# SCH_V2.net
KiCad netlist of a schematic drawn in Altium Designer
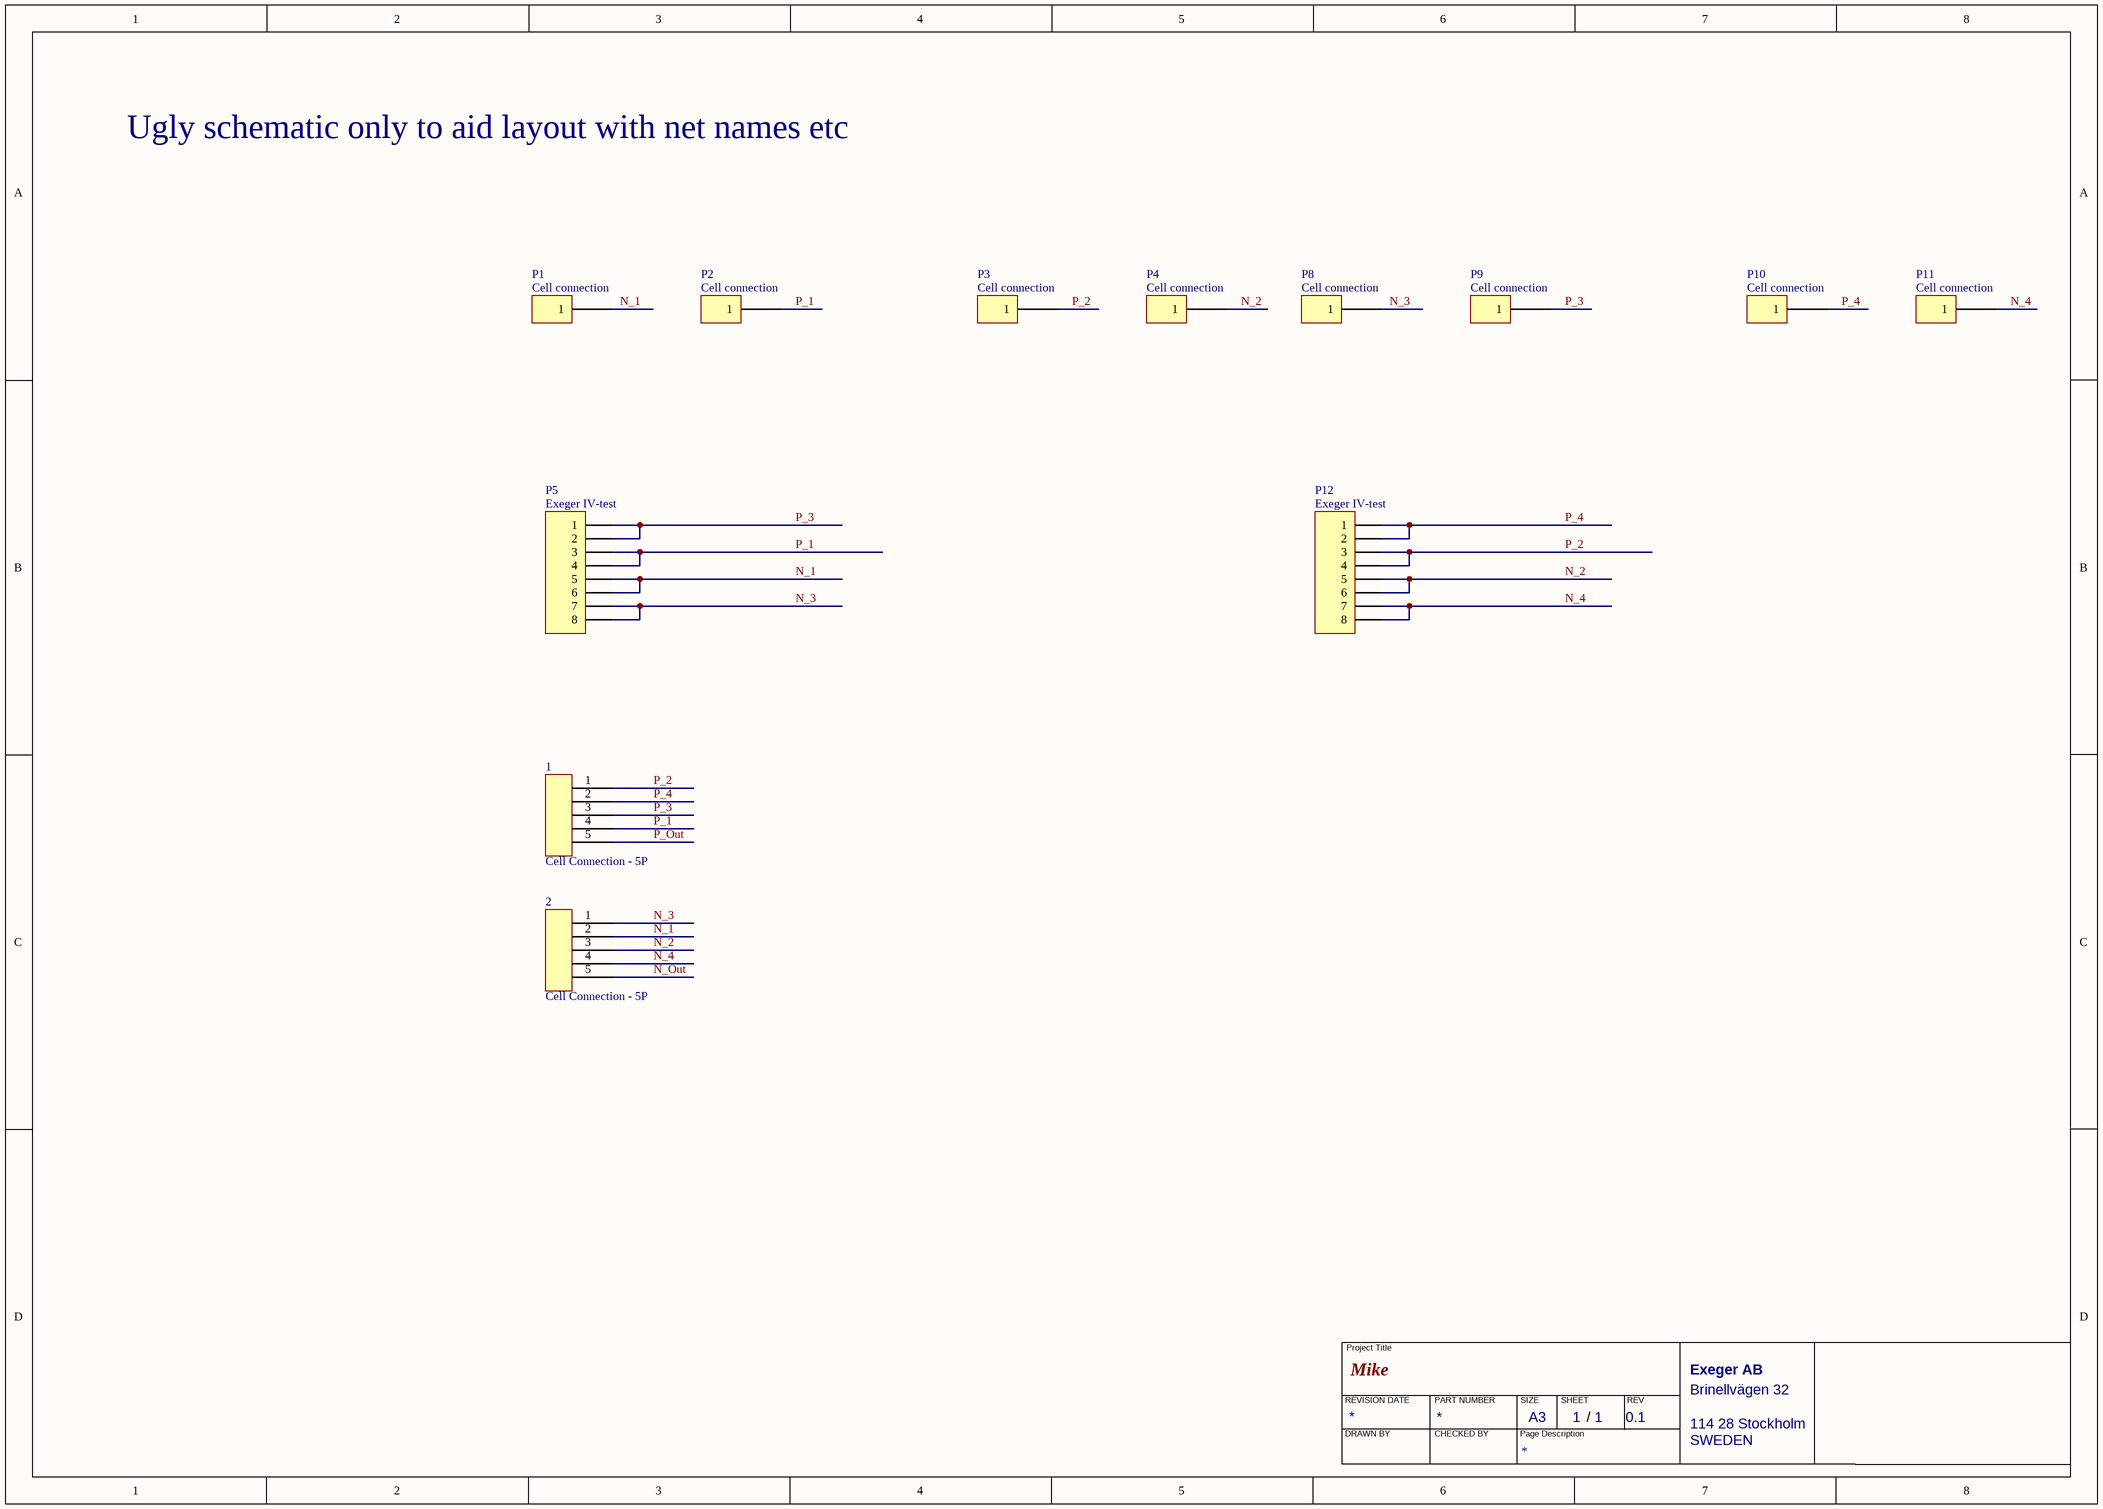
[diagram p0: SCH_V2.SchDoc]

(export (version "E")
  (design (tool "Eeschema 10.0.6"))
  (components
    (comp (ref "1")
      (value "Cell Connection - 5P")
      (footprint "4-To-1-Connector")
      (libsource (lib "Flex_SCH_symbols") (part "Cell Connection - 5P"))
    )
    (comp (ref "2")
      (value "Cell Connection - 5P")
      (footprint "4-To-1-Connector")
      (libsource (lib "Flex_SCH_symbols") (part "Cell Connection - 5P"))
    )
    (comp (ref "P1")
      (value "Cell connection")
      (footprint "Cell_pad_4mm_SM0.5mm")
      (libsource (lib "Flex_SCH_symbols") (part "Cell connection 1P"))
    )
    (comp (ref "P2")
      (value "Cell connection")
      (footprint "Cell_pad_4mm_SM0.5mm")
      (libsource (lib "Flex_SCH_symbols") (part "Cell connection 1P"))
    )
    (comp (ref "P3")
      (value "Cell connection")
      (footprint "Cell_pad_4mm_SM0.5mm")
      (libsource (lib "Flex_SCH_symbols") (part "Cell connection 1P"))
    )
    (comp (ref "P4")
      (value "Cell connection")
      (footprint "Cell_pad_4mm_SM0.5mm")
      (libsource (lib "Flex_SCH_symbols") (part "Cell connection 1P"))
    )
    (comp (ref "P5")
      (value "Exeger IV-test")
      (footprint "EXEGER_IV_8_PIN_NO_STIFF_ISOL_0.4")
      (description "Header, 8-Pin")
      (libsource (lib "Miscellaneous Connectors") (part "Header 8"))
    )
    (comp (ref "P8")
      (value "Cell connection")
      (footprint "Cell_pad_4mm_SM0.5mm")
      (libsource (lib "Flex_SCH_symbols") (part "Cell connection 1P"))
    )
    (comp (ref "P9")
      (value "Cell connection")
      (footprint "Cell_pad_4mm_SM0.5mm")
      (libsource (lib "Flex_SCH_symbols") (part "Cell connection 1P"))
    )
    (comp (ref "P10")
      (value "Cell connection")
      (footprint "Cell_pad_4mm_SM0.5mm")
      (libsource (lib "Flex_SCH_symbols") (part "Cell connection 1P"))
    )
    (comp (ref "P11")
      (value "Cell connection")
      (footprint "Cell_pad_4mm_SM0.5mm")
      (libsource (lib "Flex_SCH_symbols") (part "Cell connection 1P"))
    )
    (comp (ref "P12")
      (value "Exeger IV-test")
      (footprint "EXEGER_IV_8_PIN_NO_STIFF_ISOL_0.4")
      (description "Header, 8-Pin")
      (libsource (lib "Miscellaneous Connectors") (part "Header 8"))
    )
  )
  (nets
    (net (code "1") (name "/N_1") (class "Default")
      (node (ref "2") (pin "2") (pintype "passive"))
      (node (ref "P1") (pin "1") (pinfunction "1_1") (pintype "passive"))
      (node (ref "P5") (pin "5") (pinfunction "5_5") (pintype "passive"))
      (node (ref "P5") (pin "6") (pinfunction "6_6") (pintype "passive"))
    )
    (net (code "2") (name "/N_2") (class "Default")
      (node (ref "2") (pin "3") (pintype "passive"))
      (node (ref "P12") (pin "5") (pinfunction "5_5") (pintype "passive"))
      (node (ref "P12") (pin "6") (pinfunction "6_6") (pintype "passive"))
      (node (ref "P4") (pin "1") (pinfunction "1_1") (pintype "passive"))
    )
    (net (code "3") (name "/N_3") (class "Default")
      (node (ref "2") (pin "1") (pintype "passive"))
      (node (ref "P5") (pin "7") (pinfunction "7_7") (pintype "passive"))
      (node (ref "P5") (pin "8") (pinfunction "8_8") (pintype "passive"))
      (node (ref "P8") (pin "1") (pinfunction "1_1") (pintype "passive"))
    )
    (net (code "4") (name "/N_4") (class "Default")
      (node (ref "2") (pin "4") (pintype "passive"))
      (node (ref "P11") (pin "1") (pinfunction "1_1") (pintype "passive"))
      (node (ref "P12") (pin "7") (pinfunction "7_7") (pintype "passive"))
      (node (ref "P12") (pin "8") (pinfunction "8_8") (pintype "passive"))
    )
    (net (code "5") (name "/N_Out") (class "Default") (node (ref "2") (pin "5") (pintype "passive")))
    (net (code "6") (name "/P_1") (class "Default")
      (node (ref "1") (pin "4") (pintype "passive"))
      (node (ref "P2") (pin "1") (pinfunction "1_1") (pintype "passive"))
      (node (ref "P5") (pin "3") (pinfunction "3_3") (pintype "passive"))
      (node (ref "P5") (pin "4") (pinfunction "4_4") (pintype "passive"))
    )
    (net (code "7") (name "/P_2") (class "Default")
      (node (ref "1") (pin "1") (pintype "passive"))
      (node (ref "P12") (pin "3") (pinfunction "3_3") (pintype "passive"))
      (node (ref "P12") (pin "4") (pinfunction "4_4") (pintype "passive"))
      (node (ref "P3") (pin "1") (pinfunction "1_1") (pintype "passive"))
    )
    (net (code "8") (name "/P_3") (class "Default")
      (node (ref "1") (pin "3") (pintype "passive"))
      (node (ref "P5") (pin "1") (pinfunction "1_1") (pintype "passive"))
      (node (ref "P5") (pin "2") (pinfunction "2_2") (pintype "passive"))
      (node (ref "P9") (pin "1") (pinfunction "1_1") (pintype "passive"))
    )
    (net (code "9") (name "/P_4") (class "Default")
      (node (ref "1") (pin "2") (pintype "passive"))
      (node (ref "P10") (pin "1") (pinfunction "1_1") (pintype "passive"))
      (node (ref "P12") (pin "1") (pinfunction "1_1") (pintype "passive"))
      (node (ref "P12") (pin "2") (pinfunction "2_2") (pintype "passive"))
    )
    (net (code "10") (name "/P_Out") (class "Default") (node (ref "1") (pin "5") (pintype "passive")))
  )
)
